# Easyeda-SCH_Water-Gauge_2025-03-23.net
KiCad netlist of a schematic drawn in EasyEDA
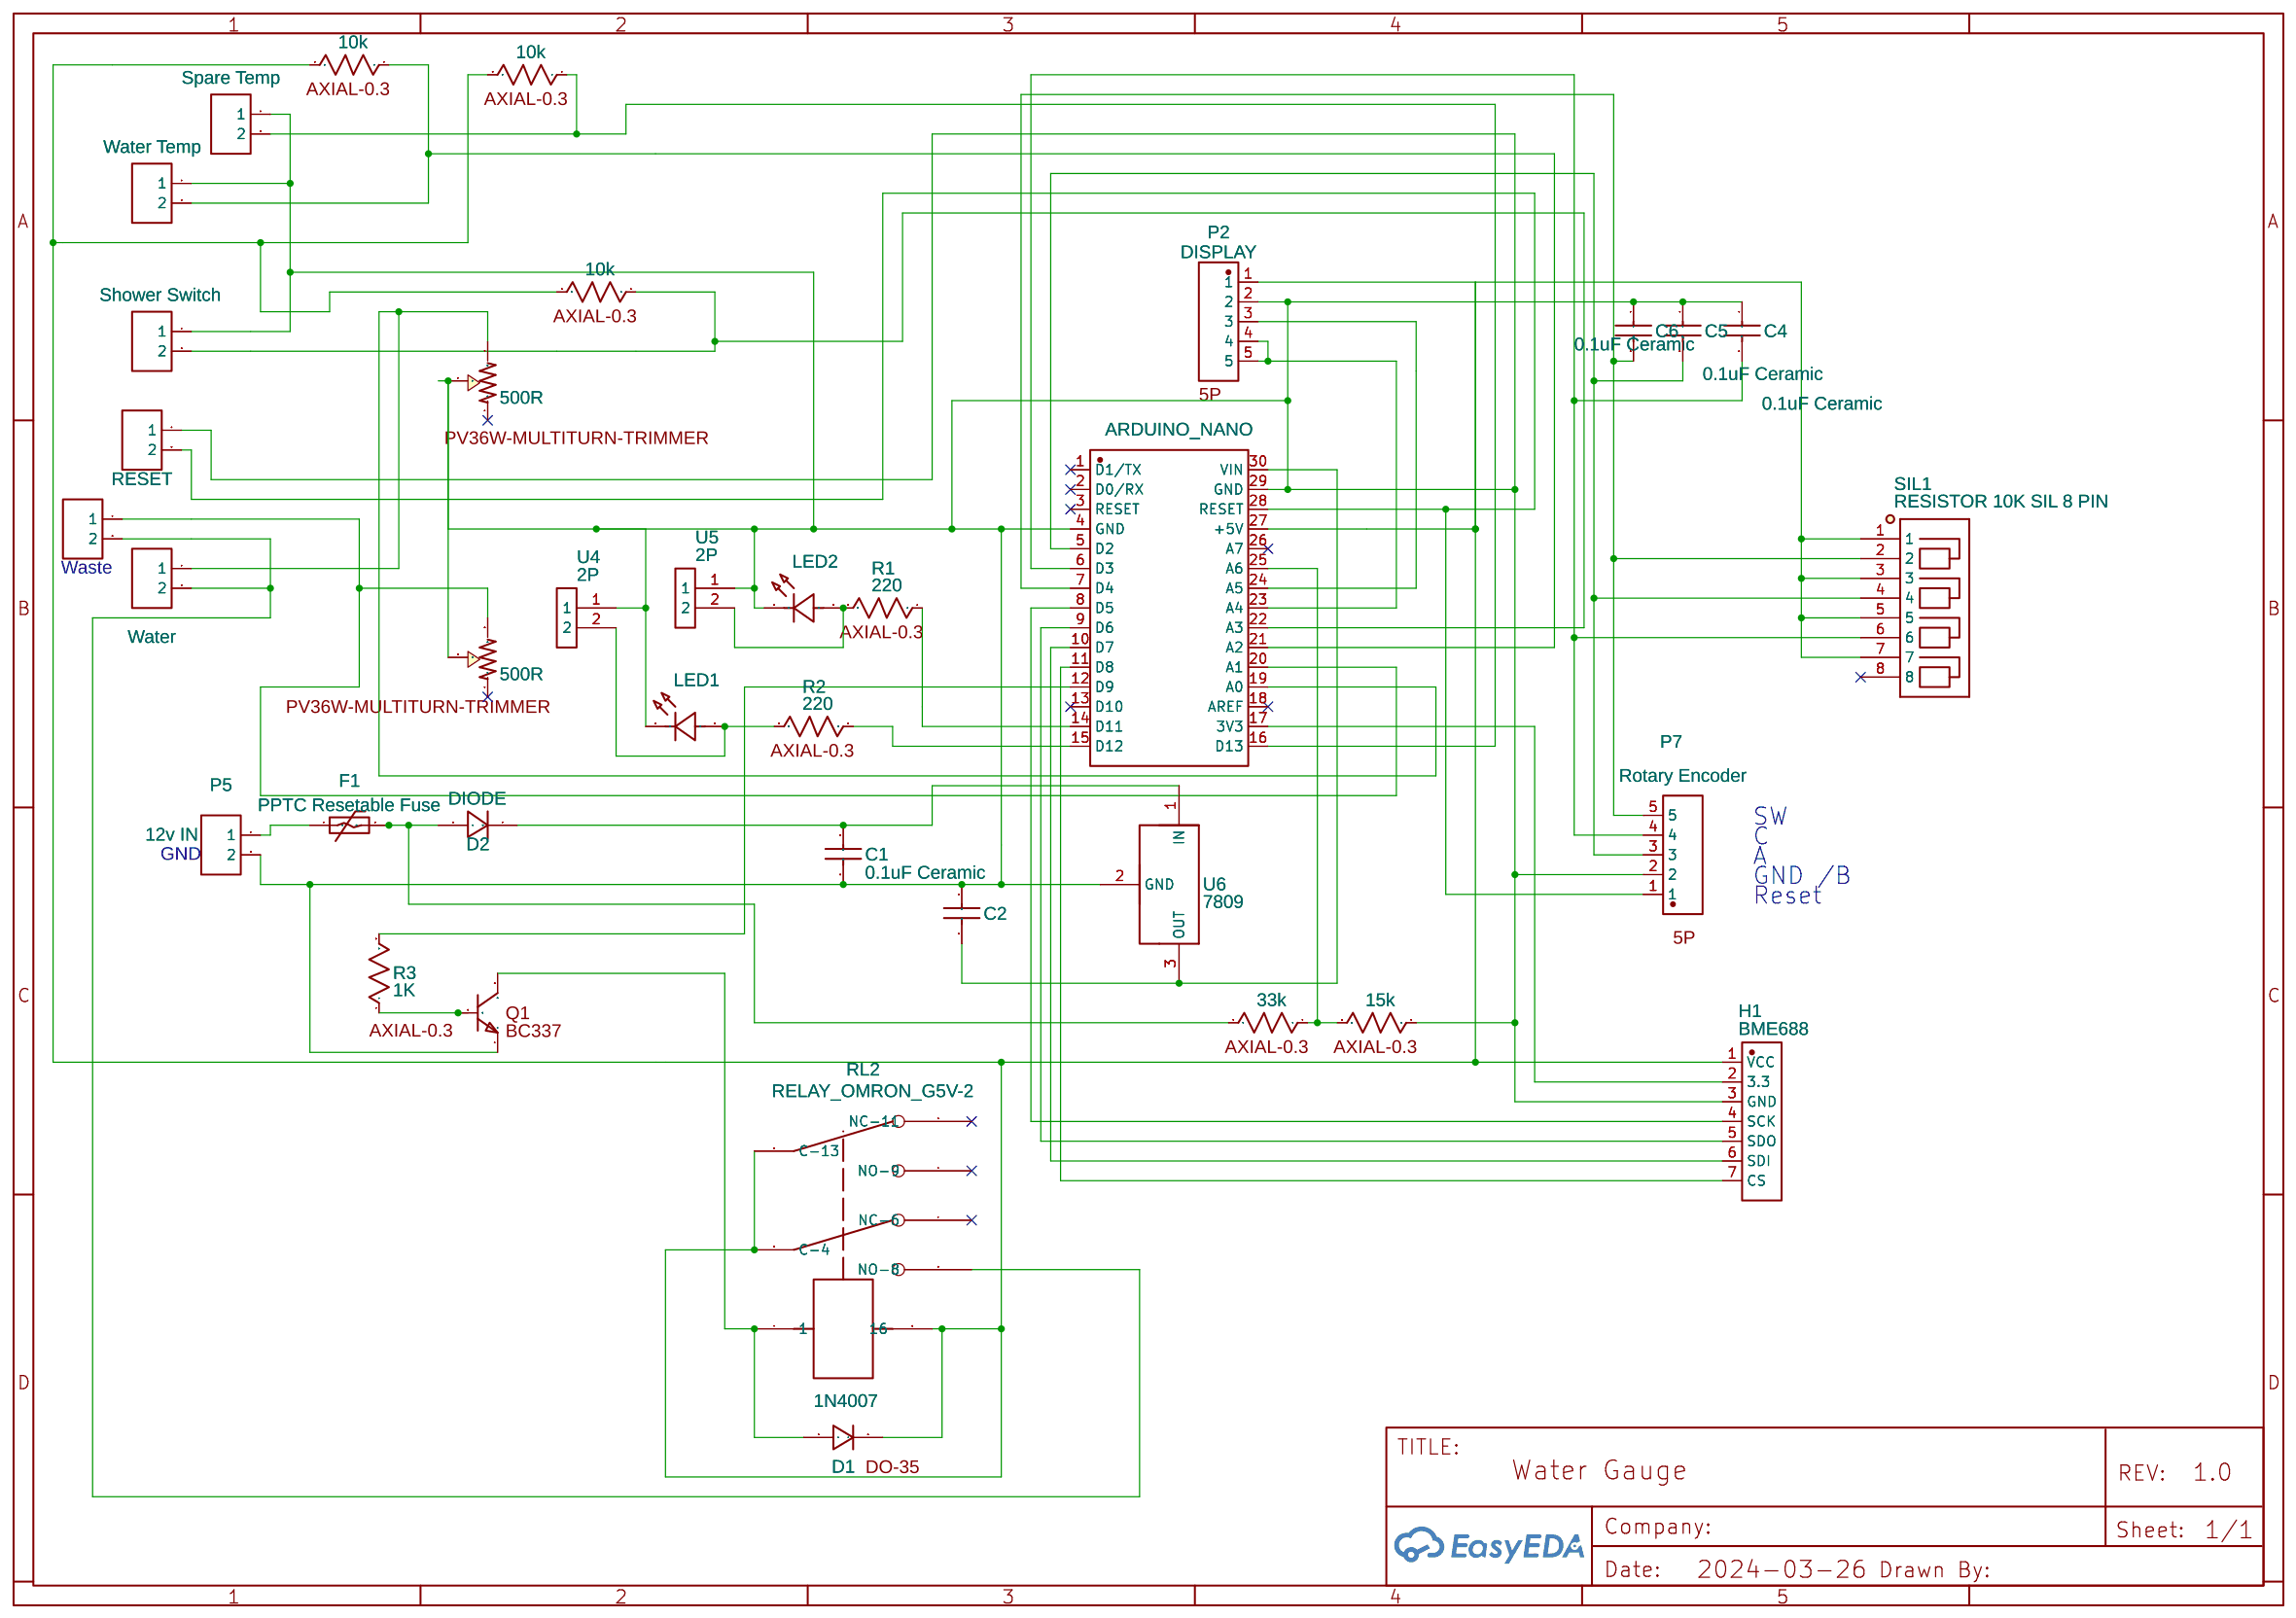
[diagram p0: schematic sheet]

(export (version "E")
  (design (tool "Eeschema 10.0.6"))
  (components
    (comp (ref "C1")
      (value "0.1uF Ceramic")
      (fields (field (name "Manufacturer Part") "Capacitor_Ceramic"))
      (libsource (lib "") (part "Capacitor_Ceramic"))
    )
    (comp (ref "C2")
      (value "0.1uF Ceramic")
      (fields (field (name "Manufacturer Part") "Capacitor_Ceramic"))
      (libsource (lib "") (part "Capacitor_Ceramic"))
    )
    (comp (ref "C4")
      (value "0.1uF Ceramic")
      (fields (field (name "Manufacturer Part") "Capacitor_Ceramic"))
      (libsource (lib "") (part "Capacitor_Ceramic"))
    )
    (comp (ref "C5")
      (value "0.1uF Ceramic")
      (fields (field (name "Manufacturer Part") "Capacitor_Ceramic"))
      (libsource (lib "") (part "Capacitor_Ceramic"))
    )
    (comp (ref "C6")
      (value "0.1uF Ceramic")
      (fields (field (name "Manufacturer Part") "Capacitor_Ceramic"))
      (libsource (lib "") (part "Capacitor_Ceramic"))
    )
    (comp (ref "D1") (value "1N4007") (libsource (lib "") (part "1N4007")))
    (comp (ref "D2")
      (value "DIODE")
      (fields (field (name "Manufacturer Part") "1N4007GR") (field (name "Manufacturer") "PINGWEI(平伟)"))
      (libsource (lib "") (part "1N4007GR"))
    )
    (comp (ref "F1")
      (value "PPTC Resetable Fuse")
      (fields (field (name "Manufacturer Part") "MF-R005-AP") (field (name "Manufacturer") "Bourns"))
      (libsource (lib "") (part "PPTC Resetable Fuse"))
    )
    (comp (ref "H1")
      (value "BME688")
      (fields (field (name "Manufacturer Part") "A2541WV-7P") (field (name "Manufacturer") "CJT(长江连接器)"))
      (libsource (lib "") (part "A2541WV-7P"))
    )
    (comp (ref "LED1")
      (value "LED2")
      (fields (field (name "Manufacturer Part") "15400394A3590") (field (name "Manufacturer") "Wurth(伍尔特)"))
      (libsource (lib "") (part "15400394A3590"))
    )
    (comp (ref "LED2")
      (value "LED1")
      (fields (field (name "Manufacturer Part") "15400394A3590") (field (name "Manufacturer") "Wurth(伍尔特)"))
      (libsource (lib "") (part "15400394A3590"))
    )
    (comp (ref "P1") (value "Water") (libsource (lib "") (part "CONN-TH_2P-P5.00_1")))
    (comp (ref "P2") (value "DISPLAY") (libsource (lib "") (part "5P")))
    (comp (ref "P3") (value "12v IN") (libsource (lib "") (part "CONN-TH_2P-P5.00_1")))
    (comp (ref "P4") (value "Shower Switch") (libsource (lib "") (part "CONN-TH_2P-P5.00_1")))
    (comp (ref "P5") (value "12v IN") (libsource (lib "") (part "CONN-TH_2P-P5.00_1")))
    (comp (ref "P6") (value "Water Temp") (libsource (lib "") (part "CONN-TH_2P-P5.00_1")))
    (comp (ref "P7") (value "Rotary Encoder") (libsource (lib "") (part "5P_1")))
    (comp (ref "P8") (value "Spare Temp") (libsource (lib "") (part "CONN-TH_2P-P5.00_1")))
    (comp (ref "Q1") (value "BD139") (libsource (lib "") (part "BC547")))
    (comp (ref "R1") (value "220") (libsource (lib "") (part "Resistor1")))
    (comp (ref "R2") (value "220") (libsource (lib "") (part "Resistor1")))
    (comp (ref "R3") (value "1K") (libsource (lib "") (part "Resistor1_1")))
    (comp (ref "R4") (value "33k") (libsource (lib "") (part "Resistor1")))
    (comp (ref "R5") (value "15k") (libsource (lib "") (part "Resistor1")))
    (comp (ref "R6") (value "10k") (libsource (lib "") (part "Resistor1")))
    (comp (ref "R9") (value "10k") (libsource (lib "") (part "Resistor1")))
    (comp (ref "R10") (value "10k") (libsource (lib "") (part "Resistor1")))
    (comp (ref "RESET") (value "12v IN") (libsource (lib "") (part "CONN-TH_2P-P5.00")))
    (comp (ref "RL2")
      (value "RELAY_OMRON_G5V-2")
      (fields (field (name "Manufacturer Part") "G5V-2") (field (name "Manufacturer") "Omron"))
      (libsource (lib "") (part "RELAY_OMRON_G5V-2"))
    )
    (comp (ref "SIL1") (value "RESISTOR 10K SIL 8 PIN") (libsource (lib "") (part "RESISTOR 10K SIL 8 PIN")))
    (comp (ref "U1") (value "ARDUINO_NANO") (libsource (lib "") (part "ARDUINO_NANO")))
    (comp (ref "U4") (value "2P") (libsource (lib "") (part "2P")))
    (comp (ref "U5") (value "2P") (libsource (lib "") (part "2P")))
    (comp (ref "U6")
      (value "7809")
      (fields (field (name "Manufacturer") "MOUSER"))
      (libsource (lib "") (part "7805"))
    )
    (comp (ref "WASTE")
      (value "500R")
      (fields (field (name "Manufacturer Part") "PV36W102C01B00") (field (name "Manufacturer") "Bourns"))
      (libsource (lib "") (part "1k_1"))
    )
    (comp (ref "WATER")
      (value "500R")
      (fields (field (name "Manufacturer Part") "PV36W102C01B00") (field (name "Manufacturer") "Bourns"))
      (libsource (lib "") (part "1k"))
    )
  )
  (nets
    (net (code "1") (name "Net-(D1-A)") (class "Default")
      (node (ref "D1") (pin "1") (pinfunction "A_1") (pintype "unspecified"))
      (node (ref "Q1") (pin "3") (pinfunction "C_3") (pintype "unspecified"))
      (node (ref "RL2") (pin "4") (pinfunction "1_4") (pintype "unspecified"))
    )
    (net (code "2") (name "Net-(D1-K)") (class "Default")
      (node (ref "D1") (pin "2") (pinfunction "K_2") (pintype "unspecified"))
      (node (ref "H1") (pin "1") (pinfunction "VCC_1") (pintype "unspecified"))
      (node (ref "P2") (pin "1") (pinfunction "1_1") (pintype "unspecified"))
      (node (ref "R10") (pin "2") (pinfunction "2_2") (pintype "unspecified"))
      (node (ref "R6") (pin "2") (pinfunction "2_2") (pintype "unspecified"))
      (node (ref "R9") (pin "2") (pinfunction "2_2") (pintype "unspecified"))
      (node (ref "RL2") (pin "3") (pinfunction "C-13_3") (pintype "unspecified"))
      (node (ref "RL2") (pin "5") (pinfunction "16_5") (pintype "unspecified"))
      (node (ref "RL2") (pin "6") (pinfunction "C-4_6") (pintype "unspecified"))
      (node (ref "SIL1") (pin "1") (pinfunction "1_1") (pintype "unspecified"))
      (node (ref "SIL1") (pin "3") (pinfunction "3_3") (pintype "unspecified"))
      (node (ref "SIL1") (pin "5") (pinfunction "5_5") (pintype "unspecified"))
      (node (ref "SIL1") (pin "7") (pinfunction "7_7") (pintype "unspecified"))
      (node (ref "U1") (pin "27") (pinfunction "+5V_27") (pintype "unspecified"))
    )
    (net (code "3") (name "Net-(D2-A)") (class "Default")
      (node (ref "D2") (pin "2") (pinfunction "A_2") (pintype "unspecified"))
      (node (ref "F1") (pin "2") (pinfunction "2_2") (pintype "unspecified"))
      (node (ref "R4") (pin "2") (pinfunction "2_2") (pintype "unspecified"))
    )
    (net (code "4") (name "Net-(D2-C)") (class "Default")
      (node (ref "C1") (pin "1") (pinfunction "1_1") (pintype "unspecified"))
      (node (ref "D2") (pin "1") (pinfunction "C_1") (pintype "unspecified"))
      (node (ref "U6") (pin "1") (pinfunction "IN_1") (pintype "unspecified"))
    )
    (net (code "5") (name "Net-(F1-Pad1)") (class "Default")
      (node (ref "F1") (pin "1") (pinfunction "1_1") (pintype "unspecified"))
      (node (ref "P5") (pin "1") (pinfunction "1_1") (pintype "unspecified"))
    )
    (net (code "6") (name "Net-(H1-3.3)") (class "Default")
      (node (ref "H1") (pin "2") (pinfunction "3.3_2") (pintype "unspecified"))
      (node (ref "U1") (pin "17") (pinfunction "3V3_17") (pintype "unspecified"))
    )
    (net (code "7") (name "Net-(H1-CS)") (class "Default")
      (node (ref "H1") (pin "7") (pinfunction "CS_7") (pintype "unspecified"))
      (node (ref "U1") (pin "11") (pinfunction "D8_11") (pintype "unspecified"))
    )
    (net (code "8") (name "Net-(H1-GND)") (class "Default")
      (node (ref "C1") (pin "2") (pinfunction "2_2") (pintype "unspecified"))
      (node (ref "C2") (pin "1") (pinfunction "1_1") (pintype "unspecified"))
      (node (ref "C4") (pin "1") (pinfunction "1_1") (pintype "unspecified"))
      (node (ref "C5") (pin "1") (pinfunction "1_1") (pintype "unspecified"))
      (node (ref "C6") (pin "1") (pinfunction "1_1") (pintype "unspecified"))
      (node (ref "H1") (pin "3") (pinfunction "GND_3") (pintype "unspecified"))
      (node (ref "LED1") (pin "1") (pinfunction "K_1") (pintype "unspecified"))
      (node (ref "LED2") (pin "1") (pinfunction "K_1") (pintype "unspecified"))
      (node (ref "P1") (pin "1") (pinfunction "1_1") (pintype "unspecified"))
      (node (ref "P2") (pin "2") (pinfunction "2_2") (pintype "unspecified"))
      (node (ref "P4") (pin "1") (pinfunction "1_1") (pintype "unspecified"))
      (node (ref "P5") (pin "2") (pinfunction "2_2") (pintype "unspecified"))
      (node (ref "P6") (pin "1") (pinfunction "1_1") (pintype "unspecified"))
      (node (ref "P7") (pin "2") (pinfunction "2_2") (pintype "unspecified"))
      (node (ref "P8") (pin "1") (pinfunction "1_1") (pintype "unspecified"))
      (node (ref "Q1") (pin "1") (pinfunction "E_1") (pintype "unspecified"))
      (node (ref "R5") (pin "1") (pinfunction "1_1") (pintype "unspecified"))
      (node (ref "U1") (pin "29") (pinfunction "GND_29") (pintype "unspecified"))
      (node (ref "U1") (pin "4") (pinfunction "GND_4") (pintype "unspecified"))
      (node (ref "U4") (pin "1") (pinfunction "1_1") (pintype "unspecified"))
      (node (ref "U5") (pin "1") (pinfunction "1_1") (pintype "unspecified"))
      (node (ref "U6") (pin "2") (pinfunction "GND_2") (pintype "unspecified"))
      (node (ref "WASTE") (pin "2") (pinfunction "2_2") (pintype "unspecified"))
      (node (ref "WATER") (pin "2") (pinfunction "2_2") (pintype "unspecified"))
    )
    (net (code "9") (name "Net-(H1-SCK)") (class "Default")
      (node (ref "H1") (pin "4") (pinfunction "SCK_4") (pintype "unspecified"))
      (node (ref "U1") (pin "8") (pinfunction "D5_8") (pintype "unspecified"))
    )
    (net (code "10") (name "Net-(H1-SDI)") (class "Default")
      (node (ref "H1") (pin "6") (pinfunction "SDI_6") (pintype "unspecified"))
      (node (ref "U1") (pin "10") (pinfunction "D7_10") (pintype "unspecified"))
    )
    (net (code "11") (name "Net-(H1-SDO)") (class "Default")
      (node (ref "H1") (pin "5") (pinfunction "SDO_5") (pintype "unspecified"))
      (node (ref "U1") (pin "9") (pinfunction "D6_9") (pintype "unspecified"))
    )
    (net (code "12") (name "Net-(LED1-A)") (class "Default")
      (node (ref "LED1") (pin "2") (pinfunction "A_2") (pintype "unspecified"))
      (node (ref "R1") (pin "2") (pinfunction "2_2") (pintype "unspecified"))
      (node (ref "U5") (pin "2") (pinfunction "2_2") (pintype "unspecified"))
    )
    (net (code "13") (name "Net-(LED2-A)") (class "Default")
      (node (ref "LED2") (pin "2") (pinfunction "A_2") (pintype "unspecified"))
      (node (ref "R2") (pin "2") (pinfunction "2_2") (pintype "unspecified"))
      (node (ref "U4") (pin "2") (pinfunction "2_2") (pintype "unspecified"))
    )
    (net (code "14") (name "Net-(P1-Pad2)") (class "Default")
      (node (ref "P1") (pin "2") (pinfunction "2_2") (pintype "unspecified"))
      (node (ref "P7") (pin "1") (pinfunction "1_1") (pintype "unspecified"))
      (node (ref "U1") (pin "28") (pinfunction "RESET_28") (pintype "unspecified"))
    )
    (net (code "15") (name "Net-(Q1-B)") (class "Default")
      (node (ref "Q1") (pin "2") (pinfunction "B_2") (pintype "unspecified"))
      (node (ref "R3") (pin "1") (pinfunction "1_1") (pintype "unspecified"))
    )
    (net (code "16") (name "Net-(RL2-NO-8)") (class "Default")
      (node (ref "P3") (pin "2") (pinfunction "2_2") (pintype "unspecified"))
      (node (ref "RESET") (pin "2") (pinfunction "2_2") (pintype "unspecified"))
      (node (ref "RL2") (pin "8") (pinfunction "NO-8_8") (pintype "unspecified"))
    )
    (net (code "17") (name "Net-(U1-A0)") (class "Default")
      (node (ref "RESET") (pin "1") (pinfunction "1_1") (pintype "unspecified"))
      (node (ref "U1") (pin "19") (pinfunction "A0_19") (pintype "unspecified"))
      (node (ref "WATER") (pin "3") (pinfunction "3_3") (pintype "unspecified"))
    )
    (net (code "18") (name "Net-(U1-A1)") (class "Default")
      (node (ref "P3") (pin "1") (pinfunction "1_1") (pintype "unspecified"))
      (node (ref "U1") (pin "20") (pinfunction "A1_20") (pintype "unspecified"))
      (node (ref "WASTE") (pin "3") (pinfunction "3_3") (pintype "unspecified"))
    )
    (net (code "19") (name "Net-(U1-A2)") (class "Default")
      (node (ref "P6") (pin "2") (pinfunction "2_2") (pintype "unspecified"))
      (node (ref "R9") (pin "1") (pinfunction "1_1") (pintype "unspecified"))
      (node (ref "U1") (pin "21") (pinfunction "A2_21") (pintype "unspecified"))
    )
    (net (code "20") (name "Net-(U1-A3)") (class "Default")
      (node (ref "P4") (pin "2") (pinfunction "2_2") (pintype "unspecified"))
      (node (ref "R10") (pin "1") (pinfunction "1_1") (pintype "unspecified"))
      (node (ref "U1") (pin "22") (pinfunction "A3_22") (pintype "unspecified"))
    )
    (net (code "21") (name "Net-(U1-A4)") (class "Default")
      (node (ref "P2") (pin "4") (pinfunction "4_4") (pintype "unspecified"))
      (node (ref "P2") (pin "5") (pinfunction "5_5") (pintype "unspecified"))
      (node (ref "U1") (pin "23") (pinfunction "A4_23") (pintype "unspecified"))
    )
    (net (code "22") (name "Net-(U1-A5)") (class "Default")
      (node (ref "P2") (pin "3") (pinfunction "3_3") (pintype "unspecified"))
      (node (ref "U1") (pin "24") (pinfunction "A5_24") (pintype "unspecified"))
    )
    (net (code "23") (name "Net-(U1-A6)") (class "Default")
      (node (ref "R4") (pin "1") (pinfunction "1_1") (pintype "unspecified"))
      (node (ref "R5") (pin "2") (pinfunction "2_2") (pintype "unspecified"))
      (node (ref "U1") (pin "25") (pinfunction "A6_25") (pintype "unspecified"))
    )
    (net (code "24") (name "Net-(U1-D2)") (class "Default")
      (node (ref "C5") (pin "2") (pinfunction "2_2") (pintype "unspecified"))
      (node (ref "P7") (pin "3") (pinfunction "3_3") (pintype "unspecified"))
      (node (ref "SIL1") (pin "4") (pinfunction "4_4") (pintype "unspecified"))
      (node (ref "U1") (pin "5") (pinfunction "D2_5") (pintype "unspecified"))
    )
    (net (code "25") (name "Net-(U1-D3)") (class "Default")
      (node (ref "C4") (pin "2") (pinfunction "2_2") (pintype "unspecified"))
      (node (ref "P7") (pin "4") (pinfunction "4_4") (pintype "unspecified"))
      (node (ref "SIL1") (pin "6") (pinfunction "6_6") (pintype "unspecified"))
      (node (ref "U1") (pin "6") (pinfunction "D3_6") (pintype "unspecified"))
    )
    (net (code "26") (name "Net-(U1-D4)") (class "Default")
      (node (ref "C6") (pin "2") (pinfunction "2_2") (pintype "unspecified"))
      (node (ref "P7") (pin "5") (pinfunction "5_5") (pintype "unspecified"))
      (node (ref "SIL1") (pin "2") (pinfunction "2_2") (pintype "unspecified"))
      (node (ref "U1") (pin "7") (pinfunction "D4_7") (pintype "unspecified"))
    )
    (net (code "27") (name "Net-(U1-D9)") (class "Default")
      (node (ref "R3") (pin "2") (pinfunction "2_2") (pintype "unspecified"))
      (node (ref "U1") (pin "12") (pinfunction "D9_12") (pintype "unspecified"))
    )
    (net (code "28") (name "Net-(U1-D11)") (class "Default")
      (node (ref "R1") (pin "1") (pinfunction "1_1") (pintype "unspecified"))
      (node (ref "U1") (pin "14") (pinfunction "D11_14") (pintype "unspecified"))
    )
    (net (code "29") (name "Net-(U1-D12)") (class "Default")
      (node (ref "R2") (pin "1") (pinfunction "1_1") (pintype "unspecified"))
      (node (ref "U1") (pin "15") (pinfunction "D12_15") (pintype "unspecified"))
    )
    (net (code "30") (name "Net-(U1-D13)") (class "Default")
      (node (ref "P8") (pin "2") (pinfunction "2_2") (pintype "unspecified"))
      (node (ref "R6") (pin "1") (pinfunction "1_1") (pintype "unspecified"))
      (node (ref "U1") (pin "16") (pinfunction "D13_16") (pintype "unspecified"))
    )
    (net (code "31") (name "Net-(U1-VIN)") (class "Default")
      (node (ref "C2") (pin "2") (pinfunction "2_2") (pintype "unspecified"))
      (node (ref "U1") (pin "30") (pinfunction "VIN_30") (pintype "unspecified"))
      (node (ref "U6") (pin "3") (pinfunction "OUT_3") (pintype "unspecified"))
    )
    (net (code "32") (name "unconnected-(RL2-NC-6-Pad7)") (class "Default")
      (node (ref "RL2") (pin "7") (pinfunction "NC-6_7") (pintype "unspecified+no_connect"))
    )
    (net (code "33") (name "unconnected-(RL2-NC-11-Pad2)") (class "Default")
      (node (ref "RL2") (pin "2") (pinfunction "NC-11_2") (pintype "unspecified+no_connect"))
    )
    (net (code "34") (name "unconnected-(RL2-NO-9-Pad1)") (class "Default")
      (node (ref "RL2") (pin "1") (pinfunction "NO-9_1") (pintype "unspecified+no_connect"))
    )
    (net (code "35") (name "unconnected-(SIL1-Pad8)") (class "Default")
      (node (ref "SIL1") (pin "8") (pinfunction "8_8") (pintype "unspecified+no_connect"))
    )
    (net (code "36") (name "unconnected-(U1-A7-Pad26)") (class "Default")
      (node (ref "U1") (pin "26") (pinfunction "A7_26") (pintype "unspecified+no_connect"))
    )
    (net (code "37") (name "unconnected-(U1-AREF-Pad18)") (class "Default")
      (node (ref "U1") (pin "18") (pinfunction "AREF_18") (pintype "unspecified+no_connect"))
    )
    (net (code "38") (name "unconnected-(U1-D0{slash}RX-Pad2)") (class "Default")
      (node (ref "U1") (pin "2") (pinfunction "D0/RX_2") (pintype "unspecified+no_connect"))
    )
    (net (code "39") (name "unconnected-(U1-D1{slash}TX-Pad1)") (class "Default")
      (node (ref "U1") (pin "1") (pinfunction "D1/TX_1") (pintype "unspecified+no_connect"))
    )
    (net (code "40") (name "unconnected-(U1-D10-Pad13)") (class "Default")
      (node (ref "U1") (pin "13") (pinfunction "D10_13") (pintype "unspecified+no_connect"))
    )
    (net (code "41") (name "unconnected-(U1-RESET-Pad3)") (class "Default")
      (node (ref "U1") (pin "3") (pinfunction "RESET_3") (pintype "unspecified+no_connect"))
    )
    (net (code "42") (name "unconnected-(WASTE-Pad1)") (class "Default")
      (node (ref "WASTE") (pin "1") (pinfunction "1_1") (pintype "unspecified+no_connect"))
    )
    (net (code "43") (name "unconnected-(WATER-Pad1)") (class "Default")
      (node (ref "WATER") (pin "1") (pinfunction "1_1") (pintype "unspecified+no_connect"))
    )
  )
)
